# nRF24L01p.net
KiCad netlist of a schematic drawn in Altium Designer
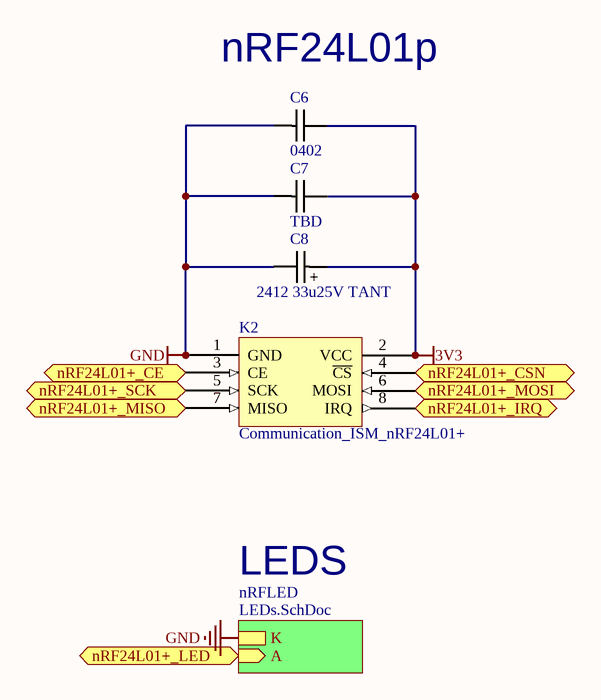
[diagram p0: nRF24L01p.SchDoc]

(export (version "E")
  (design (tool "Eeschema 10.0.6"))
  (components
    (comp (ref "C6")
      (value "0402")
      (footprint "0402C-TBD")
      (description "CAPACITOR 0402 CERAMIC")
      (libsource (lib "vh_altium_library") (part "0402C-TBD"))
    )
    (comp (ref "C7")
      (value "TBD")
      (footprint "1210C-GENERIC")
      (description "CAPACITOR 1210 CERAMIC VALUE TO BE DETERMINED")
      (libsource (lib "RVA_Altium_Library") (part "Passives_Capacitors_1210_1210C-TBD"))
    )
    (comp (ref "C8")
      (value "2412 33u25V TANT")
      (footprint "2412C+_TANTAL-33u25V")
      (libsource (lib "RVA_Altium_Library") (part "2412C-TANTAL SIZE C-33u25V"))
    )
    (comp (ref "K2")
      (value "Communication_ISM_nRF24L01+")
      (footprint "nRF24L01+_SMD")
      (description "nRF24L01+")
      (libsource (lib "RVA_Altium_Library") (part "Communication_ISM_nRF24L01+"))
    )
  )
  (nets
    (net (code "1") (name "/nRF24L01+_CE") (class "Default")
      (node (ref "K2") (pin "3") (pinfunction "CE_3") (pintype "input"))
    )
    (net (code "2") (name "/nRF24L01+_CSN") (class "Default")
      (node (ref "K2") (pin "4") (pinfunction "~{CS}_4") (pintype "input"))
    )
    (net (code "3") (name "/nRF24L01+_IRQ") (class "Default")
      (node (ref "K2") (pin "8") (pinfunction "IRQ_8") (pintype "output"))
    )
    (net (code "5") (name "/nRF24L01+_MISO") (class "Default")
      (node (ref "K2") (pin "7") (pinfunction "MISO_7") (pintype "input"))
    )
    (net (code "6") (name "/nRF24L01+_MOSI") (class "Default")
      (node (ref "K2") (pin "6") (pinfunction "MOSI_6") (pintype "input"))
    )
    (net (code "7") (name "/nRF24L01+_SCK") (class "Default")
      (node (ref "K2") (pin "5") (pinfunction "SCK_5") (pintype "input"))
    )
    (net (code "8") (name "3V3") (class "Default")
      (node (ref "C6") (pin "2") (pintype "passive"))
      (node (ref "C7") (pin "2") (pintype "passive"))
      (node (ref "C8") (pin "1") (pintype "passive"))
      (node (ref "K2") (pin "2") (pinfunction "VCC_2") (pintype "power_in"))
    )
    (net (code "9") (name "GND") (class "Default")
      (node (ref "C6") (pin "1") (pintype "passive"))
      (node (ref "C7") (pin "1") (pintype "passive"))
      (node (ref "C8") (pin "2") (pintype "passive"))
      (node (ref "K2") (pin "1") (pinfunction "GND_1") (pintype "power_in"))
    )
  )
)
